# daughterboard.net
KiCad netlist of a schematic drawn in Altium Designer
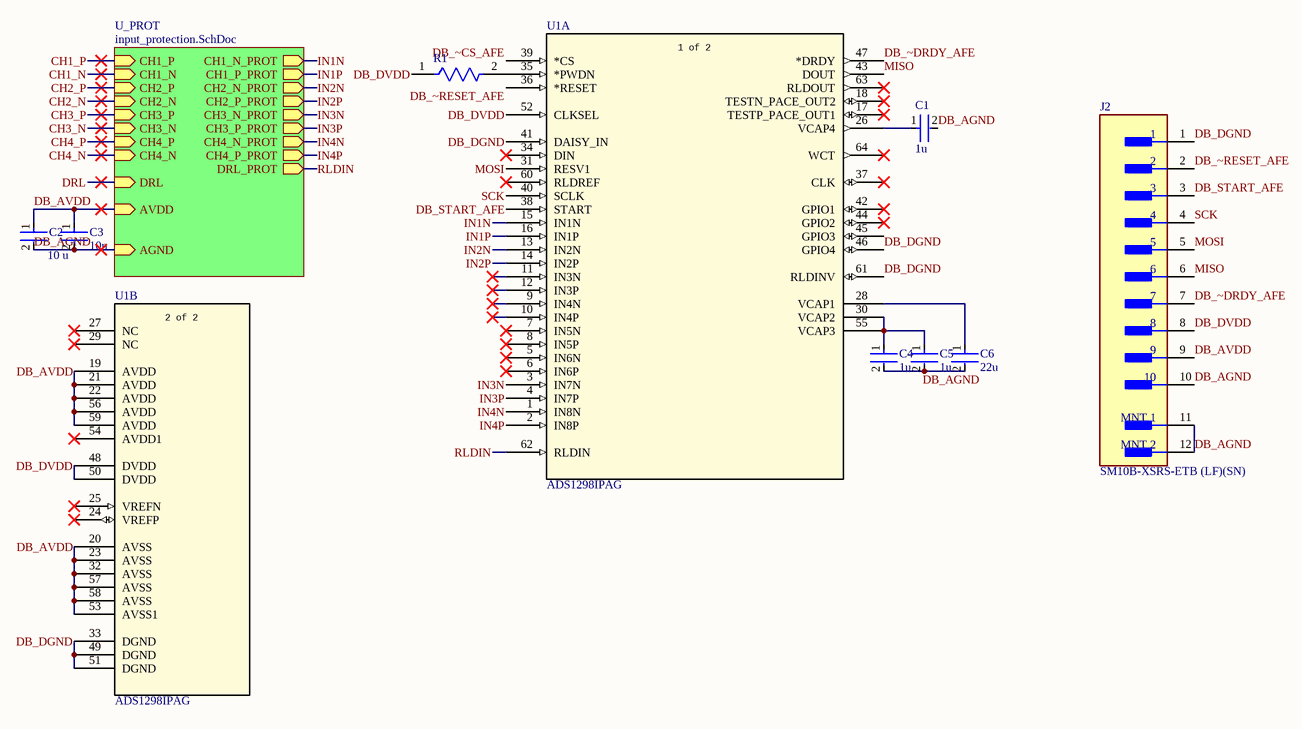
[diagram p0: daughterboard.SchDoc]

(export (version "E")
  (design (tool "Eeschema 10.0.6"))
  (components
    (comp (ref "C1")
      (value "1u")
      (footprint "FP-CC1206-1_25-MFG")
      (description "CC1206 1 uF X7R 10.00%16 V")
      (fields (field (name "TOLERANCE") "0.1") (field (name "MANUFACTURER") "Yageo"))
      (libsource (lib "Altium Content Vault") (part "11868f565c42a9108669ba33697ecf6"))
    )
    (comp (ref "C2")
      (value "10 u")
      (footprint "FP-ZRB15X-0_22-MFG")
      (libsource (lib "Altium Content Vault") (part "b4654b650e69147ec39a6b967a45e02"))
    )
    (comp (ref "C3")
      (value "10n")
      (footprint "FP-C0805C103K8RACAUTO-MFG")
      (description "C0805C103K8RACAUTO Cap, 0.01UF, 10V, Mlcc, 0805 Rohs Compliant: Yes")
      (fields (field (name "TOLERANCE") "10%"))
      (libsource (lib "Altium Content Vault") (part "b4654b650e69147ec39a6b967a45e02"))
    )
    (comp (ref "C4")
      (value "1u")
      (footprint "FP-CC1206-1_25-MFG")
      (description "CC1206 1 uF X7R 10.00%16 V")
      (fields (field (name "TOLERANCE") "0.1") (field (name "MANUFACTURER") "Yageo"))
      (libsource (lib "Altium Content Vault") (part "11868f565c42a9108669ba33697ecf6"))
    )
    (comp (ref "C5")
      (value "1u")
      (footprint "FP-CC1206-1_25-MFG")
      (description "CC1206 1 uF X7R 10.00%16 V")
      (fields (field (name "TOLERANCE") "0.1") (field (name "MANUFACTURER") "Yageo"))
      (libsource (lib "Altium Content Vault") (part "11868f565c42a9108669ba33697ecf6"))
    )
    (comp (ref "C6")
      (value "22u")
      (footprint "FP-GCJ31C-0_3-MFG")
      (description "Cap Ceramic 22uF 10V X7R 20% Pad SMD 1206 Soft Termination  +125°C Automotive T/R")
      (libsource (lib "Altium Content Vault") (part "b4654b650e69147ec39a6b967a45e02"))
    )
    (comp (ref "J2")
      (value "SM10B-XSRS-ETB (LF)(SN)")
      (footprint "FP-SM10B-XSRS-ETB_LF_SN-MFG")
      (description "CONN HEADER SMD R/A 10POS 0.6MM")
      (libsource (lib "Altium Content Vault") (part "75b8bc8596cc75ee3b2e8049366f7d6"))
    )
    (comp (ref "R1")
      (value "10k - RN73R2BTTD1001F25")
      (footprint "FP-RN73R2B-MFG")
      (description "1kΩ ±1% 0.25W, 1/4W Chip Resistor 1206 (3216 Metric) Moisture Resistant Thin Film")
      (libsource (lib "Altium Content Vault") (part "1029c3af85768c4190bb7ad29bc67b5"))
    )
    (comp (ref "U1")
      (value "ADS1298IPAG")
      (footprint "PAG64")
      (description "8-Channel 24-bit ADC With Integrated ECG Front End 64-TQFP -40 to 85")
      (fields (field (name "COPYRIGHT") "Copyright (C) 2026 Ultra Librarian. All rights reserved."))
      (libsource (lib "ADS1298IPAG") (part "ADS1298IPAG"))
    )
  )
  (nets
    (net (code "9") (name "/DB_AGND") (class "Default")
      (node (ref "C1") (pin "2") (pinfunction "2_2") (pintype "passive"))
      (node (ref "C2") (pin "2") (pinfunction "2_2") (pintype "passive"))
      (node (ref "C3") (pin "2") (pinfunction "2_2") (pintype "passive"))
      (node (ref "C4") (pin "2") (pinfunction "2_2") (pintype "passive"))
      (node (ref "C5") (pin "2") (pinfunction "2_2") (pintype "passive"))
      (node (ref "C6") (pin "2") (pinfunction "2_2") (pintype "passive"))
      (node (ref "J2") (pin "10") (pinfunction "10_10") (pintype "passive"))
      (node (ref "J2") (pin "11") (pinfunction "MNT_1_11") (pintype "passive"))
      (node (ref "J2") (pin "12") (pinfunction "MNT_2_12") (pintype "passive"))
    )
    (net (code "10") (name "/DB_AVDD") (class "Default")
      (node (ref "C2") (pin "1") (pinfunction "1_1") (pintype "passive"))
      (node (ref "C3") (pin "1") (pinfunction "1_1") (pintype "passive"))
      (node (ref "J2") (pin "9") (pinfunction "9_9") (pintype "passive"))
      (node (ref "U1") (pin "19") (pinfunction "AVDD_19") (pintype "power_in"))
      (node (ref "U1") (pin "20") (pinfunction "AVSS_20") (pintype "power_in"))
      (node (ref "U1") (pin "21") (pinfunction "AVDD_21") (pintype "power_in"))
      (node (ref "U1") (pin "22") (pinfunction "AVDD_22") (pintype "power_in"))
      (node (ref "U1") (pin "23") (pinfunction "AVSS_23") (pintype "power_in"))
      (node (ref "U1") (pin "32") (pinfunction "AVSS_32") (pintype "power_in"))
      (node (ref "U1") (pin "53") (pinfunction "AVSS1_53") (pintype "power_in"))
      (node (ref "U1") (pin "56") (pinfunction "AVDD_56") (pintype "power_in"))
      (node (ref "U1") (pin "57") (pinfunction "AVSS_57") (pintype "power_in"))
      (node (ref "U1") (pin "58") (pinfunction "AVSS_58") (pintype "power_in"))
      (node (ref "U1") (pin "59") (pinfunction "AVDD_59") (pintype "power_in"))
    )
    (net (code "11") (name "/DB_DGND") (class "Default")
      (node (ref "J2") (pin "1") (pinfunction "1_1") (pintype "passive"))
      (node (ref "U1") (pin "33") (pinfunction "DGND_33") (pintype "power_in"))
      (node (ref "U1") (pin "41") (pinfunction "DAISY_IN_41") (pintype "input"))
      (node (ref "U1") (pin "46") (pinfunction "GPIO4_46") (pintype "bidirectional"))
      (node (ref "U1") (pin "49") (pinfunction "DGND_49") (pintype "power_in"))
      (node (ref "U1") (pin "51") (pinfunction "DGND_51") (pintype "power_in"))
      (node (ref "U1") (pin "61") (pinfunction "RLDINV_61") (pintype "bidirectional"))
    )
    (net (code "12") (name "/DB_DVDD") (class "Default")
      (node (ref "J2") (pin "8") (pinfunction "8_8") (pintype "passive"))
      (node (ref "R1") (pin "1") (pinfunction "1_1") (pintype "passive"))
      (node (ref "U1") (pin "48") (pinfunction "DVDD_48") (pintype "power_in"))
      (node (ref "U1") (pin "50") (pinfunction "DVDD_50") (pintype "power_in"))
      (node (ref "U1") (pin "52") (pinfunction "CLKSEL_52") (pintype "input"))
    )
    (net (code "13") (name "/DB_START_AFE") (class "Default")
      (node (ref "J2") (pin "3") (pinfunction "3_3") (pintype "passive"))
      (node (ref "U1") (pin "38") (pinfunction "START_38") (pintype "input"))
    )
    (net (code "14") (name "/DB_~CS_AFE") (class "Default")
      (node (ref "U1") (pin "39") (pinfunction "*CS_39") (pintype "input"))
    )
    (net (code "15") (name "/DB_~DRDY_AFE") (class "Default")
      (node (ref "J2") (pin "7") (pinfunction "7_7") (pintype "passive"))
      (node (ref "U1") (pin "47") (pinfunction "*DRDY_47") (pintype "output"))
    )
    (net (code "16") (name "/DB_~RESET_AFE") (class "Default")
      (node (ref "J2") (pin "2") (pinfunction "2_2") (pintype "passive"))
      (node (ref "U1") (pin "36") (pinfunction "*RESET_36") (pintype "input"))
    )
    (net (code "18") (name "/IN1N") (class "Default")
      (node (ref "U1") (pin "15") (pinfunction "IN1N_15") (pintype "input"))
    )
    (net (code "19") (name "/IN1P") (class "Default")
      (node (ref "U1") (pin "16") (pinfunction "IN1P_16") (pintype "input"))
    )
    (net (code "20") (name "/IN2N") (class "Default")
      (node (ref "U1") (pin "13") (pinfunction "IN2N_13") (pintype "input"))
    )
    (net (code "21") (name "/IN2P") (class "Default")
      (node (ref "U1") (pin "14") (pinfunction "IN2P_14") (pintype "input"))
    )
    (net (code "22") (name "/IN3N") (class "Default")
      (node (ref "U1") (pin "3") (pinfunction "IN7N_3") (pintype "input"))
    )
    (net (code "23") (name "/IN3P") (class "Default")
      (node (ref "U1") (pin "4") (pinfunction "IN7P_4") (pintype "input"))
    )
    (net (code "24") (name "/IN4N") (class "Default")
      (node (ref "U1") (pin "1") (pinfunction "IN8N_1") (pintype "input"))
    )
    (net (code "25") (name "/IN4P") (class "Default")
      (node (ref "U1") (pin "2") (pinfunction "IN8P_2") (pintype "input"))
    )
    (net (code "26") (name "/MISO") (class "Default")
      (node (ref "J2") (pin "6") (pinfunction "6_6") (pintype "passive"))
      (node (ref "U1") (pin "43") (pinfunction "DOUT_43") (pintype "output"))
    )
    (net (code "27") (name "/MOSI") (class "Default")
      (node (ref "J2") (pin "5") (pinfunction "5_5") (pintype "passive"))
      (node (ref "U1") (pin "31") (pinfunction "RESV1_31") (pintype "input"))
    )
    (net (code "28") (name "/RLDIN") (class "Default")
      (node (ref "U1") (pin "62") (pinfunction "RLDIN_62") (pintype "input"))
    )
    (net (code "29") (name "/SCK") (class "Default")
      (node (ref "J2") (pin "4") (pinfunction "4_4") (pintype "passive"))
      (node (ref "U1") (pin "40") (pinfunction "SCLK_40") (pintype "input"))
    )
    (net (code "30") (name "Net-(U1A-*PWDN)") (class "Default")
      (node (ref "R1") (pin "2") (pinfunction "2_2") (pintype "passive"))
      (node (ref "U1") (pin "35") (pinfunction "*PWDN_35") (pintype "input"))
    )
    (net (code "31") (name "Net-(U1A-VCAP1)") (class "Default")
      (node (ref "C6") (pin "1") (pinfunction "1_1") (pintype "passive"))
      (node (ref "U1") (pin "28") (pinfunction "VCAP1_28") (pintype "passive"))
    )
    (net (code "32") (name "Net-(U1A-VCAP2)") (class "Default")
      (node (ref "C4") (pin "1") (pinfunction "1_1") (pintype "passive"))
      (node (ref "C5") (pin "1") (pinfunction "1_1") (pintype "passive"))
      (node (ref "U1") (pin "30") (pinfunction "VCAP2_30") (pintype "passive"))
      (node (ref "U1") (pin "55") (pinfunction "VCAP3_55") (pintype "passive"))
    )
    (net (code "33") (name "Net-(U1A-VCAP4)") (class "Default")
      (node (ref "C1") (pin "1") (pinfunction "1_1") (pintype "passive"))
      (node (ref "U1") (pin "26") (pinfunction "VCAP4_26") (pintype "output"))
    )
    (net (code "34") (name "unconnected-(U1A-CLK-Pad37)") (class "Default")
      (node (ref "U1") (pin "37") (pinfunction "CLK_37") (pintype "bidirectional+no_connect"))
    )
    (net (code "35") (name "unconnected-(U1A-DIN-Pad34)") (class "Default")
      (node (ref "U1") (pin "34") (pinfunction "DIN_34") (pintype "input+no_connect"))
    )
    (net (code "36") (name "unconnected-(U1A-GPIO1-Pad42)") (class "Default")
      (node (ref "U1") (pin "42") (pinfunction "GPIO1_42") (pintype "bidirectional+no_connect"))
    )
    (net (code "37") (name "unconnected-(U1A-GPIO2-Pad44)") (class "Default")
      (node (ref "U1") (pin "44") (pinfunction "GPIO2_44") (pintype "bidirectional+no_connect"))
    )
    (net (code "38") (name "unconnected-(U1A-GPIO3-Pad45)") (class "Default")
      (node (ref "U1") (pin "45") (pinfunction "GPIO3_45") (pintype "bidirectional"))
    )
    (net (code "39") (name "unconnected-(U1A-IN3N-Pad11)") (class "Default")
      (node (ref "U1") (pin "11") (pinfunction "IN3N_11") (pintype "input+no_connect"))
    )
    (net (code "40") (name "unconnected-(U1A-IN3P-Pad12)") (class "Default")
      (node (ref "U1") (pin "12") (pinfunction "IN3P_12") (pintype "input+no_connect"))
    )
    (net (code "41") (name "unconnected-(U1A-IN4N-Pad9)") (class "Default")
      (node (ref "U1") (pin "9") (pinfunction "IN4N_9") (pintype "input+no_connect"))
    )
    (net (code "42") (name "unconnected-(U1A-IN4P-Pad10)") (class "Default")
      (node (ref "U1") (pin "10") (pinfunction "IN4P_10") (pintype "input+no_connect"))
    )
    (net (code "43") (name "unconnected-(U1A-IN5N-Pad7)") (class "Default")
      (node (ref "U1") (pin "7") (pinfunction "IN5N_7") (pintype "input+no_connect"))
    )
    (net (code "44") (name "unconnected-(U1A-IN5P-Pad8)") (class "Default")
      (node (ref "U1") (pin "8") (pinfunction "IN5P_8") (pintype "input+no_connect"))
    )
    (net (code "45") (name "unconnected-(U1A-IN6N-Pad5)") (class "Default")
      (node (ref "U1") (pin "5") (pinfunction "IN6N_5") (pintype "input+no_connect"))
    )
    (net (code "46") (name "unconnected-(U1A-IN6P-Pad6)") (class "Default")
      (node (ref "U1") (pin "6") (pinfunction "IN6P_6") (pintype "input+no_connect"))
    )
    (net (code "47") (name "unconnected-(U1A-RLDOUT-Pad63)") (class "Default")
      (node (ref "U1") (pin "63") (pinfunction "RLDOUT_63") (pintype "output+no_connect"))
    )
    (net (code "48") (name "unconnected-(U1A-RLDREF-Pad60)") (class "Default")
      (node (ref "U1") (pin "60") (pinfunction "RLDREF_60") (pintype "input+no_connect"))
    )
    (net (code "49") (name "unconnected-(U1A-TESTN_PACE_OUT2-Pad18)") (class "Default")
      (node (ref "U1") (pin "18") (pinfunction "TESTN_PACE_OUT2_18") (pintype "bidirectional+no_connect"))
    )
    (net (code "50") (name "unconnected-(U1A-TESTP_PACE_OUT1-Pad17)") (class "Default")
      (node (ref "U1") (pin "17") (pinfunction "TESTP_PACE_OUT1_17") (pintype "bidirectional+no_connect"))
    )
    (net (code "51") (name "unconnected-(U1A-WCT-Pad64)") (class "Default")
      (node (ref "U1") (pin "64") (pinfunction "WCT_64") (pintype "output+no_connect"))
    )
    (net (code "52") (name "unconnected-(U1B-AVDD1-Pad54)") (class "Default")
      (node (ref "U1") (pin "54") (pinfunction "AVDD1_54") (pintype "power_in+no_connect"))
    )
    (net (code "53") (name "unconnected-(U1B-NC-Pad27)") (class "Default")
      (node (ref "U1") (pin "27") (pinfunction "NC_27") (pintype "passive+no_connect"))
    )
    (net (code "54") (name "unconnected-(U1B-NC-Pad29)") (class "Default")
      (node (ref "U1") (pin "29") (pinfunction "NC_29") (pintype "passive+no_connect"))
    )
    (net (code "55") (name "unconnected-(U1B-VREFN-Pad25)") (class "Default")
      (node (ref "U1") (pin "25") (pinfunction "VREFN_25") (pintype "input+no_connect"))
    )
    (net (code "56") (name "unconnected-(U1B-VREFP-Pad24)") (class "Default")
      (node (ref "U1") (pin "24") (pinfunction "VREFP_24") (pintype "bidirectional+no_connect"))
    )
  )
)
